# stm32f107rct7_devbrd.net
KiCad netlist of a schematic drawn in Altium Designer
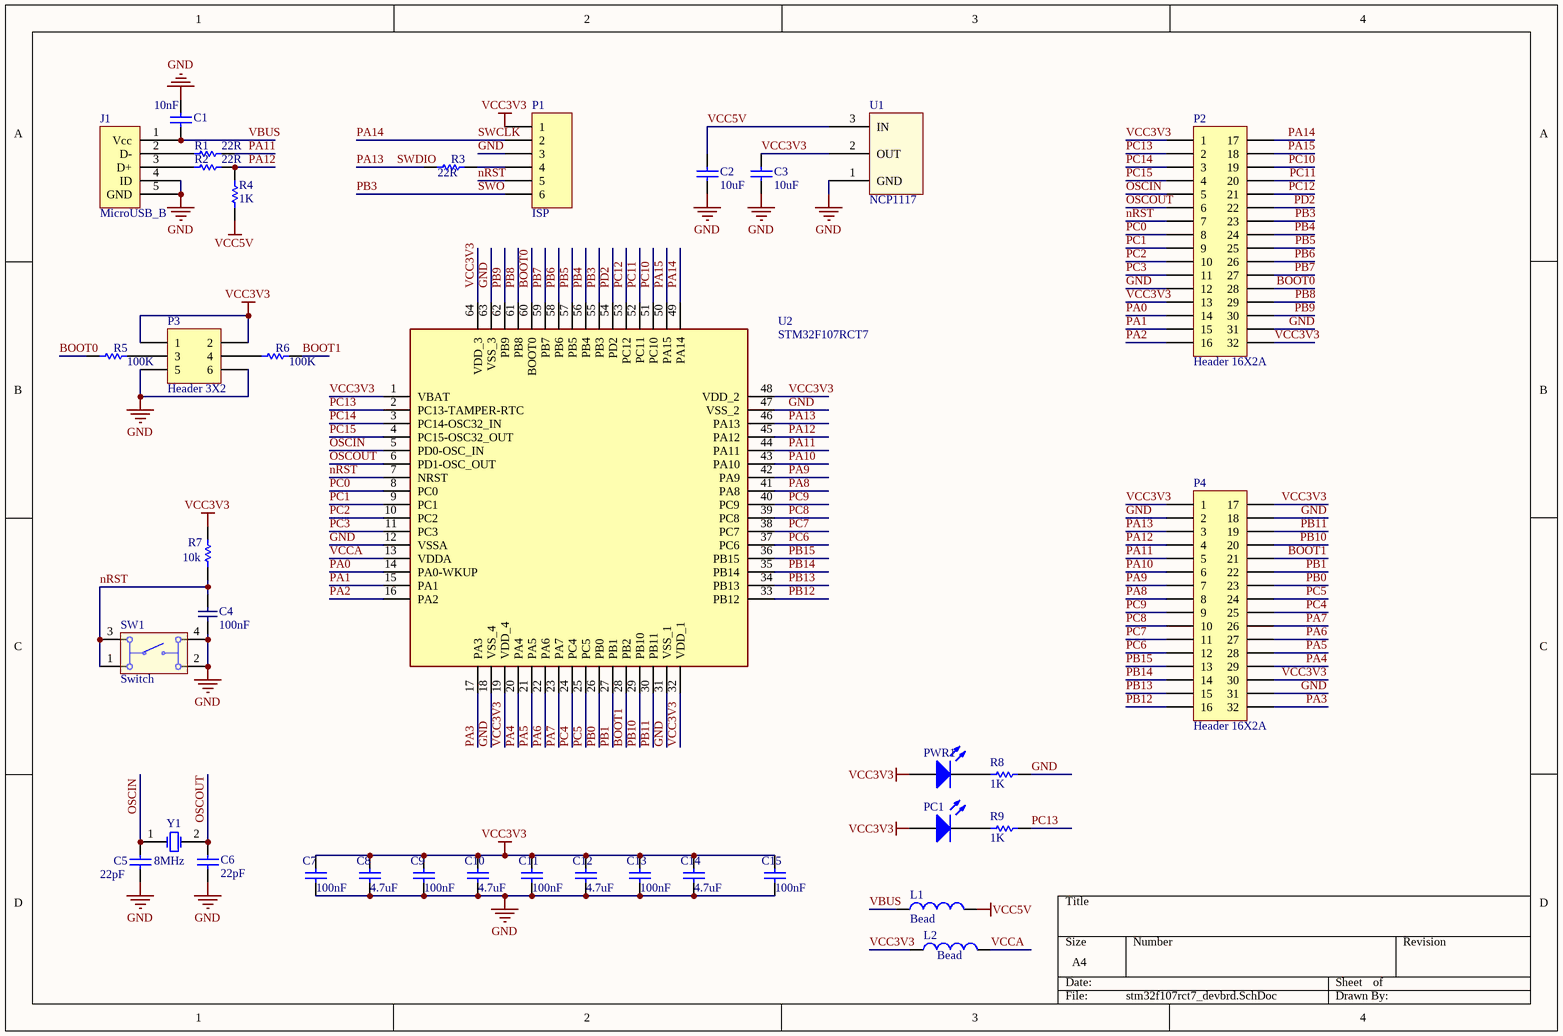
[diagram p0: stm32f107rct7_devbrd.SchDoc]

(export (version "E")
  (design (tool "Eeschema 10.0.6"))
  (components
    (comp (ref "C1")
      (value "10nF")
      (footprint "SMD0805_CAP")
      (description "Capacitor (Semiconductor SIM Model)")
      (fields (field (name "PUBLISHER") "Altium Limited"))
      (libsource (lib "Miscellaneous Devices") (part "Cap Semi"))
    )
    (comp (ref "C2")
      (value "10uF")
      (footprint "SMD0805_CAP")
      (description "Capacitor (Semiconductor SIM Model)")
      (fields (field (name "PUBLISHER") "Altium Limited"))
      (libsource (lib "Miscellaneous Devices") (part "Cap Semi"))
    )
    (comp (ref "C3")
      (value "10uF")
      (footprint "SMD0805_CAP")
      (description "Capacitor (Semiconductor SIM Model)")
      (fields (field (name "PUBLISHER") "Altium Limited"))
      (libsource (lib "Miscellaneous Devices") (part "Cap Semi"))
    )
    (comp (ref "C4")
      (value "100nF")
      (footprint "SMD0805_CAP")
      (description "Capacitor (Semiconductor SIM Model)")
      (libsource (lib "SRV8") (part "Cap"))
    )
    (comp (ref "C5")
      (value "22pF")
      (footprint "SMD0805_CAP")
      (description "Capacitor (Semiconductor SIM Model)")
      (fields (field (name "PUBLISHER") "Altium Limited"))
      (libsource (lib "Miscellaneous Devices") (part "Cap Semi"))
    )
    (comp (ref "C6")
      (value "22pF")
      (footprint "SMD0805_CAP")
      (description "Capacitor (Semiconductor SIM Model)")
      (fields (field (name "PUBLISHER") "Altium Limited"))
      (libsource (lib "Miscellaneous Devices") (part "Cap Semi"))
    )
    (comp (ref "C7")
      (value "100nF")
      (footprint "SMD0805_CAP")
      (description "Capacitor (Semiconductor SIM Model)")
      (fields (field (name "PUBLISHER") "Altium Limited"))
      (libsource (lib "Miscellaneous Devices") (part "Cap Semi"))
    )
    (comp (ref "C8")
      (value "4.7uF")
      (footprint "SMD0805_CAP")
      (description "Capacitor (Semiconductor SIM Model)")
      (fields (field (name "PUBLISHER") "Altium Limited"))
      (libsource (lib "Miscellaneous Devices") (part "Cap Semi"))
    )
    (comp (ref "C9")
      (value "100nF")
      (footprint "SMD0805_CAP")
      (description "Capacitor (Semiconductor SIM Model)")
      (fields (field (name "PUBLISHER") "Altium Limited"))
      (libsource (lib "Miscellaneous Devices") (part "Cap Semi"))
    )
    (comp (ref "C10")
      (value "4.7uF")
      (footprint "SMD0805_CAP")
      (description "Capacitor (Semiconductor SIM Model)")
      (fields (field (name "PUBLISHER") "Altium Limited"))
      (libsource (lib "Miscellaneous Devices") (part "Cap Semi"))
    )
    (comp (ref "C11")
      (value "100nF")
      (footprint "SMD0805_CAP")
      (description "Capacitor (Semiconductor SIM Model)")
      (fields (field (name "PUBLISHER") "Altium Limited"))
      (libsource (lib "Miscellaneous Devices") (part "Cap Semi"))
    )
    (comp (ref "C12")
      (value "4.7uF")
      (footprint "SMD0805_CAP")
      (description "Capacitor (Semiconductor SIM Model)")
      (fields (field (name "PUBLISHER") "Altium Limited"))
      (libsource (lib "Miscellaneous Devices") (part "Cap Semi"))
    )
    (comp (ref "C13")
      (value "100nF")
      (footprint "SMD0805_CAP")
      (description "Capacitor (Semiconductor SIM Model)")
      (fields (field (name "PUBLISHER") "Altium Limited"))
      (libsource (lib "Miscellaneous Devices") (part "Cap Semi"))
    )
    (comp (ref "C14")
      (value "4.7uF")
      (footprint "SMD0805_CAP")
      (description "Capacitor (Semiconductor SIM Model)")
      (fields (field (name "PUBLISHER") "Altium Limited"))
      (libsource (lib "Miscellaneous Devices") (part "Cap Semi"))
    )
    (comp (ref "C15")
      (value "100nF")
      (footprint "SMD0805_CAP")
      (description "Capacitor (Semiconductor SIM Model)")
      (fields (field (name "PUBLISHER") "Altium Limited"))
      (libsource (lib "Miscellaneous Devices") (part "Cap Semi"))
    )
    (comp (ref "J1")
      (value "MicroUSB_B")
      (footprint "micro_usb_molex_105017-0001")
      (libsource (lib "stm32_m3_component") (part "MicroUSB_B"))
    )
    (comp (ref "L1")
      (value "Bead")
      (footprint "SMD0805")
      (description "Inductor")
      (fields (field (name "PUBLISHER") "Altium Limited"))
      (libsource (lib "Miscellaneous Devices") (part "Inductor"))
    )
    (comp (ref "L2")
      (value "Bead")
      (footprint "SMD0805")
      (description "Inductor")
      (fields (field (name "PUBLISHER") "Altium Limited"))
      (libsource (lib "Miscellaneous Devices") (part "Inductor"))
    )
    (comp (ref "P1")
      (value "ISP")
      (footprint "ISP")
      (description "Header, 6-Pin")
      (fields (field (name "PUBLISHER") "Altium Limited"))
      (libsource (lib "Miscellaneous Connectors") (part "MHDR1X6"))
    )
    (comp (ref "P2")
      (value "Header 16X2A")
      (footprint "HDR2X16_CEN")
      (description "Header, 16-Pin, Dual row")
      (fields (field (name "PUBLISHER") "Altium Limited"))
      (libsource (lib "Miscellaneous Connectors") (part "Header 16X2A"))
    )
    (comp (ref "P3")
      (value "Header 3X2")
      (footprint "HDR2X3")
      (description "Header, 3-Pin, Dual row")
      (fields (field (name "PUBLISHER") "Altium Limited"))
      (libsource (lib "Miscellaneous Connectors") (part "Header 3X2"))
    )
    (comp (ref "P4")
      (value "Header 16X2A")
      (footprint "HDR2X16_CEN")
      (description "Header, 16-Pin, Dual row")
      (fields (field (name "PUBLISHER") "Altium Limited"))
      (libsource (lib "Miscellaneous Connectors") (part "Header 16X2A"))
    )
    (comp (ref "PC1")
      (value "LED0")
      (footprint "LED")
      (description "Typical INFRARED GaAs LED")
      (fields (field (name "PUBLISHER") "Altium Limited"))
      (libsource (lib "Miscellaneous Devices") (part "LED0"))
    )
    (comp (ref "PWR1")
      (value "LED0")
      (footprint "LED")
      (description "Typical INFRARED GaAs LED")
      (fields (field (name "PUBLISHER") "Altium Limited"))
      (libsource (lib "Miscellaneous Devices") (part "LED0"))
    )
    (comp (ref "R1")
      (value "22R")
      (footprint "SMD0805")
      (description "Semiconductor Resistor")
      (fields (field (name "PUBLISHER") "Altium Limited"))
      (libsource (lib "Miscellaneous Devices") (part "Res Semi"))
    )
    (comp (ref "R2")
      (value "22R")
      (footprint "SMD0805")
      (description "Semiconductor Resistor")
      (fields (field (name "PUBLISHER") "Altium Limited"))
      (libsource (lib "Miscellaneous Devices") (part "Res Semi"))
    )
    (comp (ref "R3")
      (value "22R")
      (footprint "SMD0805")
      (description "Semiconductor Resistor")
      (fields (field (name "PUBLISHER") "Altium Limited"))
      (libsource (lib "Miscellaneous Devices") (part "Res Semi"))
    )
    (comp (ref "R4")
      (value "1K")
      (footprint "SMD0805")
      (description "Semiconductor Resistor")
      (fields (field (name "PUBLISHER") "Altium Limited"))
      (libsource (lib "Miscellaneous Devices") (part "Res Semi"))
    )
    (comp (ref "R5")
      (value "100K")
      (footprint "SMD0805")
      (description "Semiconductor Resistor")
      (fields (field (name "PUBLISHER") "Altium Limited"))
      (libsource (lib "Miscellaneous Devices") (part "Res Semi"))
    )
    (comp (ref "R6")
      (value "100K")
      (footprint "SMD0805")
      (description "Semiconductor Resistor")
      (fields (field (name "PUBLISHER") "Altium Limited"))
      (libsource (lib "Miscellaneous Devices") (part "Res Semi"))
    )
    (comp (ref "R7")
      (value "10k")
      (footprint "SMD0805")
      (description "Semiconductor Resistor")
      (fields (field (name "Comment") "100K"))
      (libsource (lib "*") (part "Res"))
    )
    (comp (ref "R8")
      (value "1K")
      (footprint "SMD0805")
      (description "Semiconductor Resistor")
      (fields (field (name "PUBLISHER") "Altium Limited"))
      (libsource (lib "Miscellaneous Devices") (part "Res Semi"))
    )
    (comp (ref "R9")
      (value "1K")
      (footprint "SMD0805")
      (description "Semiconductor Resistor")
      (fields (field (name "PUBLISHER") "Altium Limited"))
      (libsource (lib "Miscellaneous Devices") (part "Res Semi"))
    )
    (comp (ref "SW1")
      (value "Switch")
      (footprint "430156050726")
      (description "WS-TATV THT Tact Switch 6X6 mm")
      (fields (field (name "PARTNUMBER") "430156050726"))
      (libsource (lib "WS-TATV THT Tact Switch 6X6 mm") (part "430156050726"))
    )
    (comp (ref "U1")
      (value "NCP1117")
      (footprint "SOT-223-2")
      (description "IC REG 5V 1A DPAC")
      (libsource (lib "stm32_m3_component") (part "NCP1117"))
    )
    (comp (ref "U2")
      (value "STM32F107RCT7")
      (footprint "stm32f107rct7_component:QFP50P1200X1200X160-64N")
      (description "Integrated Circuit")
      (fields (field (name "MOUSER2 PART NUMBER") "511-STM32F107RCT7"))
      (libsource (lib "stm32f107rct7_component") (part "STM32F107RCT7"))
    )
    (comp (ref "Y1")
      (value "8MHz")
      (footprint "XTAL")
      (description "Crystal Oscillator 8MHz")
      (fields (field (name "PUBLISHER") "Altium Limited"))
      (libsource (lib "Miscellaneous Devices") (part "XTAL"))
    )
  )
  (nets
    (net (code "1") (name "/BOOT0") (class "Default")
      (node (ref "P2") (pin "28") (pinfunction "28_28") (pintype "passive"))
      (node (ref "R5") (pin "1") (pinfunction "1_1") (pintype "passive"))
      (node (ref "U2") (pin "60") (pinfunction "BOOT0_60") (pintype "passive"))
    )
    (net (code "2") (name "/BOOT1") (class "Default")
      (node (ref "P4") (pin "21") (pinfunction "21_21") (pintype "passive"))
      (node (ref "R6") (pin "2") (pinfunction "2_2") (pintype "passive"))
      (node (ref "U2") (pin "28") (pinfunction "PB2_28") (pintype "passive"))
    )
    (net (code "3") (name "/OSCIN") (class "Default")
      (node (ref "C5") (pin "1") (pinfunction "1_1") (pintype "passive"))
      (node (ref "P2") (pin "5") (pinfunction "5_5") (pintype "passive"))
      (node (ref "U2") (pin "5") (pinfunction "PD0-OSC_IN_5") (pintype "passive"))
      (node (ref "Y1") (pin "1") (pinfunction "OSC1_1") (pintype "passive"))
    )
    (net (code "4") (name "/OSCOUT") (class "Default")
      (node (ref "C6") (pin "1") (pinfunction "1_1") (pintype "passive"))
      (node (ref "P2") (pin "6") (pinfunction "6_6") (pintype "passive"))
      (node (ref "U2") (pin "6") (pinfunction "PD1-OSC_OUT_6") (pintype "passive"))
      (node (ref "Y1") (pin "2") (pinfunction "OSC2_2") (pintype "passive"))
    )
    (net (code "5") (name "/PA0") (class "Default")
      (node (ref "P2") (pin "14") (pinfunction "14_14") (pintype "passive"))
      (node (ref "U2") (pin "14") (pinfunction "PA0-WKUP_14") (pintype "passive"))
    )
    (net (code "6") (name "/PA1") (class "Default")
      (node (ref "P2") (pin "15") (pinfunction "15_15") (pintype "passive"))
      (node (ref "U2") (pin "15") (pinfunction "PA1_15") (pintype "passive"))
    )
    (net (code "7") (name "/PA2") (class "Default")
      (node (ref "P2") (pin "16") (pinfunction "16_16") (pintype "passive"))
      (node (ref "U2") (pin "16") (pinfunction "PA2_16") (pintype "passive"))
    )
    (net (code "8") (name "/PA3") (class "Default")
      (node (ref "P4") (pin "32") (pinfunction "32_32") (pintype "passive"))
      (node (ref "U2") (pin "17") (pinfunction "PA3_17") (pintype "passive"))
    )
    (net (code "9") (name "/PA4") (class "Default")
      (node (ref "P4") (pin "29") (pinfunction "29_29") (pintype "passive"))
      (node (ref "U2") (pin "20") (pinfunction "PA4_20") (pintype "passive"))
    )
    (net (code "10") (name "/PA5") (class "Default")
      (node (ref "P4") (pin "28") (pinfunction "28_28") (pintype "passive"))
      (node (ref "U2") (pin "21") (pinfunction "PA5_21") (pintype "passive"))
    )
    (net (code "11") (name "/PA6") (class "Default")
      (node (ref "P4") (pin "27") (pinfunction "27_27") (pintype "passive"))
      (node (ref "U2") (pin "22") (pinfunction "PA6_22") (pintype "passive"))
    )
    (net (code "12") (name "/PA7") (class "Default")
      (node (ref "P4") (pin "26") (pinfunction "26_26") (pintype "passive"))
      (node (ref "U2") (pin "23") (pinfunction "PA7_23") (pintype "passive"))
    )
    (net (code "13") (name "/PA8") (class "Default")
      (node (ref "P4") (pin "8") (pinfunction "8_8") (pintype "passive"))
      (node (ref "U2") (pin "41") (pinfunction "PA8_41") (pintype "passive"))
    )
    (net (code "14") (name "/PA9") (class "Default")
      (node (ref "P4") (pin "7") (pinfunction "7_7") (pintype "passive"))
      (node (ref "U2") (pin "42") (pinfunction "PA9_42") (pintype "passive"))
    )
    (net (code "15") (name "/PA10") (class "Default")
      (node (ref "P4") (pin "6") (pinfunction "6_6") (pintype "passive"))
      (node (ref "U2") (pin "43") (pinfunction "PA10_43") (pintype "passive"))
    )
    (net (code "16") (name "/PA11") (class "Default")
      (node (ref "P4") (pin "5") (pinfunction "5_5") (pintype "passive"))
      (node (ref "R1") (pin "2") (pinfunction "2_2") (pintype "passive"))
      (node (ref "U2") (pin "44") (pinfunction "PA11_44") (pintype "passive"))
    )
    (net (code "17") (name "/PA12") (class "Default")
      (node (ref "P4") (pin "4") (pinfunction "4_4") (pintype "passive"))
      (node (ref "R2") (pin "2") (pinfunction "2_2") (pintype "passive"))
      (node (ref "R4") (pin "2") (pinfunction "2_2") (pintype "passive"))
      (node (ref "U2") (pin "45") (pinfunction "PA12_45") (pintype "passive"))
    )
    (net (code "18") (name "/PA13") (class "Default")
      (node (ref "P4") (pin "3") (pinfunction "3_3") (pintype "passive"))
      (node (ref "R3") (pin "1") (pinfunction "1_1") (pintype "passive"))
      (node (ref "U2") (pin "46") (pinfunction "PA13_46") (pintype "passive"))
    )
    (net (code "19") (name "/PA14") (class "Default")
      (node (ref "P1") (pin "2") (pinfunction "2_2") (pintype "passive"))
      (node (ref "P2") (pin "17") (pinfunction "17_17") (pintype "passive"))
      (node (ref "U2") (pin "49") (pinfunction "PA14_49") (pintype "passive"))
    )
    (net (code "20") (name "/PA15") (class "Default")
      (node (ref "P2") (pin "18") (pinfunction "18_18") (pintype "passive"))
      (node (ref "U2") (pin "50") (pinfunction "PA15_50") (pintype "passive"))
    )
    (net (code "21") (name "/PB0") (class "Default")
      (node (ref "P4") (pin "23") (pinfunction "23_23") (pintype "passive"))
      (node (ref "U2") (pin "26") (pinfunction "PB0_26") (pintype "passive"))
    )
    (net (code "22") (name "/PB1") (class "Default")
      (node (ref "P4") (pin "22") (pinfunction "22_22") (pintype "passive"))
      (node (ref "U2") (pin "27") (pinfunction "PB1_27") (pintype "passive"))
    )
    (net (code "23") (name "/PB3") (class "Default")
      (node (ref "P1") (pin "6") (pinfunction "6_6") (pintype "passive"))
      (node (ref "P2") (pin "23") (pinfunction "23_23") (pintype "passive"))
      (node (ref "U2") (pin "55") (pinfunction "PB3_55") (pintype "passive"))
    )
    (net (code "24") (name "/PB4") (class "Default")
      (node (ref "P2") (pin "24") (pinfunction "24_24") (pintype "passive"))
      (node (ref "U2") (pin "56") (pinfunction "PB4_56") (pintype "passive"))
    )
    (net (code "25") (name "/PB5") (class "Default")
      (node (ref "P2") (pin "25") (pinfunction "25_25") (pintype "passive"))
      (node (ref "U2") (pin "57") (pinfunction "PB5_57") (pintype "passive"))
    )
    (net (code "26") (name "/PB6") (class "Default")
      (node (ref "P2") (pin "26") (pinfunction "26_26") (pintype "passive"))
      (node (ref "U2") (pin "58") (pinfunction "PB6_58") (pintype "passive"))
    )
    (net (code "27") (name "/PB7") (class "Default")
      (node (ref "P2") (pin "27") (pinfunction "27_27") (pintype "passive"))
      (node (ref "U2") (pin "59") (pinfunction "PB7_59") (pintype "passive"))
    )
    (net (code "28") (name "/PB8") (class "Default")
      (node (ref "P2") (pin "29") (pinfunction "29_29") (pintype "passive"))
      (node (ref "U2") (pin "61") (pinfunction "PB8_61") (pintype "passive"))
    )
    (net (code "29") (name "/PB9") (class "Default")
      (node (ref "P2") (pin "30") (pinfunction "30_30") (pintype "passive"))
      (node (ref "U2") (pin "62") (pinfunction "PB9_62") (pintype "passive"))
    )
    (net (code "30") (name "/PB10") (class "Default")
      (node (ref "P4") (pin "20") (pinfunction "20_20") (pintype "passive"))
      (node (ref "U2") (pin "29") (pinfunction "PB10_29") (pintype "passive"))
    )
    (net (code "31") (name "/PB11") (class "Default")
      (node (ref "P4") (pin "19") (pinfunction "19_19") (pintype "passive"))
      (node (ref "U2") (pin "30") (pinfunction "PB11_30") (pintype "passive"))
    )
    (net (code "32") (name "/PB12") (class "Default")
      (node (ref "P4") (pin "16") (pinfunction "16_16") (pintype "passive"))
      (node (ref "U2") (pin "33") (pinfunction "PB12_33") (pintype "passive"))
    )
    (net (code "33") (name "/PB13") (class "Default")
      (node (ref "P4") (pin "15") (pinfunction "15_15") (pintype "passive"))
      (node (ref "U2") (pin "34") (pinfunction "PB13_34") (pintype "passive"))
    )
    (net (code "34") (name "/PB14") (class "Default")
      (node (ref "P4") (pin "14") (pinfunction "14_14") (pintype "passive"))
      (node (ref "U2") (pin "35") (pinfunction "PB14_35") (pintype "passive"))
    )
    (net (code "35") (name "/PB15") (class "Default")
      (node (ref "P4") (pin "13") (pinfunction "13_13") (pintype "passive"))
      (node (ref "U2") (pin "36") (pinfunction "PB15_36") (pintype "passive"))
    )
    (net (code "36") (name "/PC0") (class "Default")
      (node (ref "P2") (pin "8") (pinfunction "8_8") (pintype "passive"))
      (node (ref "U2") (pin "8") (pinfunction "PC0_8") (pintype "passive"))
    )
    (net (code "37") (name "/PC1") (class "Default")
      (node (ref "P2") (pin "9") (pinfunction "9_9") (pintype "passive"))
      (node (ref "U2") (pin "9") (pinfunction "PC1_9") (pintype "passive"))
    )
    (net (code "38") (name "/PC2") (class "Default")
      (node (ref "P2") (pin "10") (pinfunction "10_10") (pintype "passive"))
      (node (ref "U2") (pin "10") (pinfunction "PC2_10") (pintype "passive"))
    )
    (net (code "39") (name "/PC3") (class "Default")
      (node (ref "P2") (pin "11") (pinfunction "11_11") (pintype "passive"))
      (node (ref "U2") (pin "11") (pinfunction "PC3_11") (pintype "passive"))
    )
    (net (code "40") (name "/PC4") (class "Default")
      (node (ref "P4") (pin "25") (pinfunction "25_25") (pintype "passive"))
      (node (ref "U2") (pin "24") (pinfunction "PC4_24") (pintype "passive"))
    )
    (net (code "41") (name "/PC5") (class "Default")
      (node (ref "P4") (pin "24") (pinfunction "24_24") (pintype "passive"))
      (node (ref "U2") (pin "25") (pinfunction "PC5_25") (pintype "passive"))
    )
    (net (code "42") (name "/PC6") (class "Default")
      (node (ref "P4") (pin "12") (pinfunction "12_12") (pintype "passive"))
      (node (ref "U2") (pin "37") (pinfunction "PC6_37") (pintype "passive"))
    )
    (net (code "43") (name "/PC7") (class "Default")
      (node (ref "P4") (pin "11") (pinfunction "11_11") (pintype "passive"))
      (node (ref "U2") (pin "38") (pinfunction "PC7_38") (pintype "passive"))
    )
    (net (code "44") (name "/PC8") (class "Default")
      (node (ref "P4") (pin "10") (pinfunction "10_10") (pintype "passive"))
      (node (ref "U2") (pin "39") (pinfunction "PC8_39") (pintype "passive"))
    )
    (net (code "45") (name "/PC9") (class "Default")
      (node (ref "P4") (pin "9") (pinfunction "9_9") (pintype "passive"))
      (node (ref "U2") (pin "40") (pinfunction "PC9_40") (pintype "passive"))
    )
    (net (code "46") (name "/PC10") (class "Default")
      (node (ref "P2") (pin "19") (pinfunction "19_19") (pintype "passive"))
      (node (ref "U2") (pin "51") (pinfunction "PC10_51") (pintype "passive"))
    )
    (net (code "47") (name "/PC11") (class "Default")
      (node (ref "P2") (pin "20") (pinfunction "20_20") (pintype "passive"))
      (node (ref "U2") (pin "52") (pinfunction "PC11_52") (pintype "passive"))
    )
    (net (code "48") (name "/PC12") (class "Default")
      (node (ref "P2") (pin "21") (pinfunction "21_21") (pintype "passive"))
      (node (ref "U2") (pin "53") (pinfunction "PC12_53") (pintype "passive"))
    )
    (net (code "49") (name "/PC13") (class "Default")
      (node (ref "P2") (pin "2") (pinfunction "2_2") (pintype "passive"))
      (node (ref "R9") (pin "1") (pinfunction "1_1") (pintype "passive"))
      (node (ref "U2") (pin "2") (pinfunction "PC13-TAMPER-RTC_2") (pintype "passive"))
    )
    (net (code "50") (name "/PC14") (class "Default")
      (node (ref "P2") (pin "3") (pinfunction "3_3") (pintype "passive"))
      (node (ref "U2") (pin "3") (pinfunction "PC14-OSC32_IN_3") (pintype "passive"))
    )
    (net (code "51") (name "/PC15") (class "Default")
      (node (ref "P2") (pin "4") (pinfunction "4_4") (pintype "passive"))
      (node (ref "U2") (pin "4") (pinfunction "PC15-OSC32_OUT_4") (pintype "passive"))
    )
    (net (code "52") (name "/PD2") (class "Default")
      (node (ref "P2") (pin "22") (pinfunction "22_22") (pintype "passive"))
      (node (ref "U2") (pin "54") (pinfunction "PD2_54") (pintype "passive"))
    )
    (net (code "53") (name "/VBUS") (class "Default")
      (node (ref "C1") (pin "1") (pinfunction "1_1") (pintype "passive"))
      (node (ref "J1") (pin "1") (pinfunction "Vcc_1") (pintype "passive"))
      (node (ref "L1") (pin "1") (pinfunction "1_1") (pintype "passive"))
    )
    (net (code "54") (name "/VCCA") (class "Default")
      (node (ref "L2") (pin "2") (pinfunction "2_2") (pintype "passive"))
      (node (ref "U2") (pin "13") (pinfunction "VDDA_13") (pintype "passive"))
    )
    (net (code "55") (name "/nRST") (class "Default")
      (node (ref "C4") (pin "1") (pinfunction "1_1") (pintype "passive"))
      (node (ref "P1") (pin "5") (pinfunction "5_5") (pintype "passive"))
      (node (ref "P2") (pin "7") (pinfunction "7_7") (pintype "passive"))
      (node (ref "R7") (pin "1") (pinfunction "1_1") (pintype "passive"))
      (node (ref "SW1") (pin "1") (pinfunction "1_1") (pintype "passive"))
      (node (ref "SW1") (pin "3") (pinfunction "3_3") (pintype "passive"))
      (node (ref "U2") (pin "7") (pinfunction "NRST_7") (pintype "passive"))
    )
    (net (code "56") (name "GND") (class "Default")
      (node (ref "C1") (pin "2") (pinfunction "2_2") (pintype "passive"))
      (node (ref "C10") (pin "1") (pinfunction "1_1") (pintype "passive"))
      (node (ref "C11") (pin "1") (pinfunction "1_1") (pintype "passive"))
      (node (ref "C12") (pin "1") (pinfunction "1_1") (pintype "passive"))
      (node (ref "C13") (pin "1") (pinfunction "1_1") (pintype "passive"))
      (node (ref "C14") (pin "1") (pinfunction "1_1") (pintype "passive"))
      (node (ref "C15") (pin "1") (pinfunction "1_1") (pintype "passive"))
      (node (ref "C2") (pin "1") (pinfunction "1_1") (pintype "passive"))
      (node (ref "C3") (pin "1") (pinfunction "1_1") (pintype "passive"))
      (node (ref "C4") (pin "2") (pinfunction "2_2") (pintype "passive"))
      (node (ref "C5") (pin "2") (pinfunction "2_2") (pintype "passive"))
      (node (ref "C6") (pin "2") (pinfunction "2_2") (pintype "passive"))
      (node (ref "C7") (pin "1") (pinfunction "1_1") (pintype "passive"))
      (node (ref "C8") (pin "1") (pinfunction "1_1") (pintype "passive"))
      (node (ref "C9") (pin "1") (pinfunction "1_1") (pintype "passive"))
      (node (ref "J1") (pin "4") (pinfunction "ID_4") (pintype "passive"))
      (node (ref "J1") (pin "5") (pinfunction "GND_5") (pintype "passive"))
      (node (ref "P1") (pin "3") (pinfunction "3_3") (pintype "passive"))
      (node (ref "P2") (pin "12") (pinfunction "12_12") (pintype "passive"))
      (node (ref "P2") (pin "31") (pinfunction "31_31") (pintype "passive"))
      (node (ref "P3") (pin "5") (pinfunction "5_5") (pintype "passive"))
      (node (ref "P3") (pin "6") (pinfunction "6_6") (pintype "passive"))
      (node (ref "P4") (pin "18") (pinfunction "18_18") (pintype "passive"))
      (node (ref "P4") (pin "2") (pinfunction "2_2") (pintype "passive"))
      (node (ref "P4") (pin "31") (pinfunction "31_31") (pintype "passive"))
      (node (ref "R8") (pin "1") (pinfunction "1_1") (pintype "passive"))
      (node (ref "SW1") (pin "2") (pinfunction "2_2") (pintype "passive"))
      (node (ref "SW1") (pin "4") (pinfunction "4_4") (pintype "passive"))
      (node (ref "U1") (pin "1") (pinfunction "GND_1") (pintype "passive"))
      (node (ref "U2") (pin "12") (pinfunction "VSSA_12") (pintype "passive"))
      (node (ref "U2") (pin "18") (pinfunction "VSS_4_18") (pintype "passive"))
      (node (ref "U2") (pin "31") (pinfunction "VSS_1_31") (pintype "passive"))
      (node (ref "U2") (pin "47") (pinfunction "VSS_2_47") (pintype "passive"))
      (node (ref "U2") (pin "63") (pinfunction "VSS_3_63") (pintype "passive"))
    )
    (net (code "57") (name "Net-(J1-D+)") (class "Default")
      (node (ref "J1") (pin "3") (pinfunction "D+_3") (pintype "passive"))
      (node (ref "R2") (pin "1") (pinfunction "1_1") (pintype "passive"))
    )
    (net (code "58") (name "Net-(J1-D-)") (class "Default")
      (node (ref "J1") (pin "2") (pinfunction "D-_2") (pintype "passive"))
      (node (ref "R1") (pin "1") (pinfunction "1_1") (pintype "passive"))
    )
    (net (code "59") (name "Net-(P1-Pad4)") (class "Default")
      (node (ref "P1") (pin "4") (pinfunction "4_4") (pintype "passive"))
      (node (ref "R3") (pin "2") (pinfunction "2_2") (pintype "passive"))
    )
    (net (code "60") (name "Net-(P3-Pad3)") (class "Default")
      (node (ref "P3") (pin "3") (pinfunction "3_3") (pintype "passive"))
      (node (ref "R5") (pin "2") (pinfunction "2_2") (pintype "passive"))
    )
    (net (code "61") (name "Net-(P3-Pad4)") (class "Default")
      (node (ref "P3") (pin "4") (pinfunction "4_4") (pintype "passive"))
      (node (ref "R6") (pin "1") (pinfunction "1_1") (pintype "passive"))
    )
    (net (code "62") (name "Net-(PC1-K)") (class "Default")
      (node (ref "PC1") (pin "2") (pinfunction "K_2") (pintype "passive"))
      (node (ref "R9") (pin "2") (pinfunction "2_2") (pintype "passive"))
    )
    (net (code "63") (name "Net-(PWR1-K)") (class "Default")
      (node (ref "PWR1") (pin "2") (pinfunction "K_2") (pintype "passive"))
      (node (ref "R8") (pin "2") (pinfunction "2_2") (pintype "passive"))
    )
    (net (code "64") (name "VCC3V3") (class "Default")
      (node (ref "C10") (pin "2") (pinfunction "2_2") (pintype "passive"))
      (node (ref "C11") (pin "2") (pinfunction "2_2") (pintype "passive"))
      (node (ref "C12") (pin "2") (pinfunction "2_2") (pintype "passive"))
      (node (ref "C13") (pin "2") (pinfunction "2_2") (pintype "passive"))
      (node (ref "C14") (pin "2") (pinfunction "2_2") (pintype "passive"))
      (node (ref "C15") (pin "2") (pinfunction "2_2") (pintype "passive"))
      (node (ref "C3") (pin "2") (pinfunction "2_2") (pintype "passive"))
      (node (ref "C7") (pin "2") (pinfunction "2_2") (pintype "passive"))
      (node (ref "C8") (pin "2") (pinfunction "2_2") (pintype "passive"))
      (node (ref "C9") (pin "2") (pinfunction "2_2") (pintype "passive"))
      (node (ref "L2") (pin "1") (pinfunction "1_1") (pintype "passive"))
      (node (ref "P1") (pin "1") (pinfunction "1_1") (pintype "passive"))
      (node (ref "P2") (pin "1") (pinfunction "1_1") (pintype "passive"))
      (node (ref "P2") (pin "13") (pinfunction "13_13") (pintype "passive"))
      (node (ref "P2") (pin "32") (pinfunction "32_32") (pintype "passive"))
      (node (ref "P3") (pin "1") (pinfunction "1_1") (pintype "passive"))
      (node (ref "P3") (pin "2") (pinfunction "2_2") (pintype "passive"))
      (node (ref "P4") (pin "1") (pinfunction "1_1") (pintype "passive"))
      (node (ref "P4") (pin "17") (pinfunction "17_17") (pintype "passive"))
      (node (ref "P4") (pin "30") (pinfunction "30_30") (pintype "passive"))
      (node (ref "PC1") (pin "1") (pinfunction "A_1") (pintype "passive"))
      (node (ref "PWR1") (pin "1") (pinfunction "A_1") (pintype "passive"))
      (node (ref "R7") (pin "2") (pinfunction "2_2") (pintype "passive"))
      (node (ref "U1") (pin "2") (pinfunction "OUT_2") (pintype "passive"))
      (node (ref "U2") (pin "1") (pinfunction "VBAT_1") (pintype "passive"))
      (node (ref "U2") (pin "19") (pinfunction "VDD_4_19") (pintype "passive"))
      (node (ref "U2") (pin "32") (pinfunction "VDD_1_32") (pintype "passive"))
      (node (ref "U2") (pin "48") (pinfunction "VDD_2_48") (pintype "passive"))
      (node (ref "U2") (pin "64") (pinfunction "VDD_3_64") (pintype "passive"))
    )
    (net (code "65") (name "VCC5V") (class "Default")
      (node (ref "C2") (pin "2") (pinfunction "2_2") (pintype "passive"))
      (node (ref "L1") (pin "2") (pinfunction "2_2") (pintype "passive"))
      (node (ref "R4") (pin "1") (pinfunction "1_1") (pintype "passive"))
      (node (ref "U1") (pin "3") (pinfunction "IN_3") (pintype "passive"))
    )
  )
)
